# board.net
KiCad netlist of a schematic drawn in EAGLE
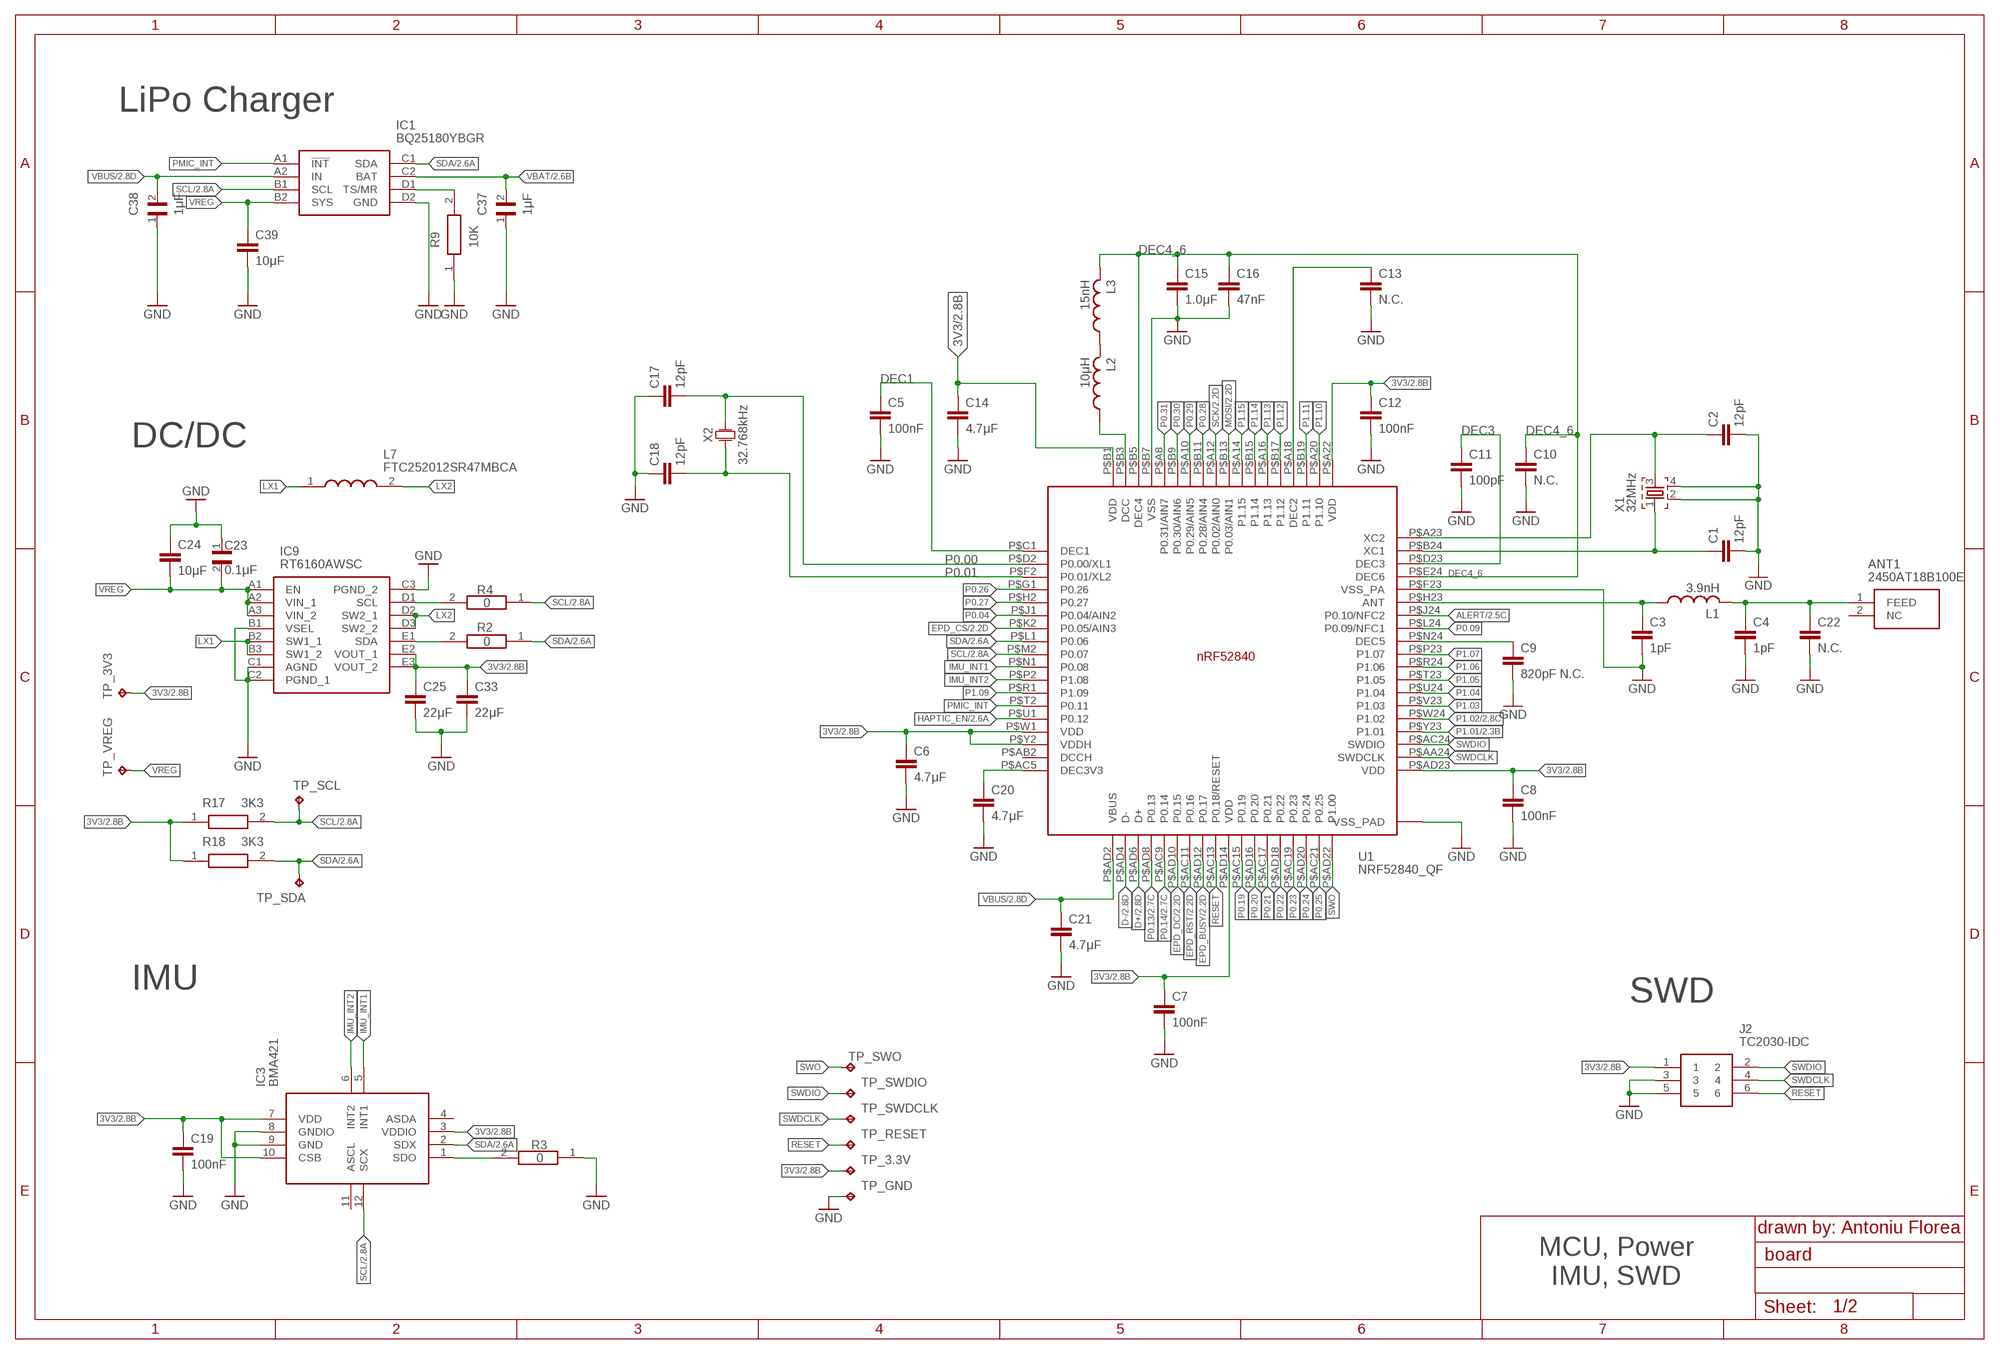
[diagram p0: schematic, sheet 1]
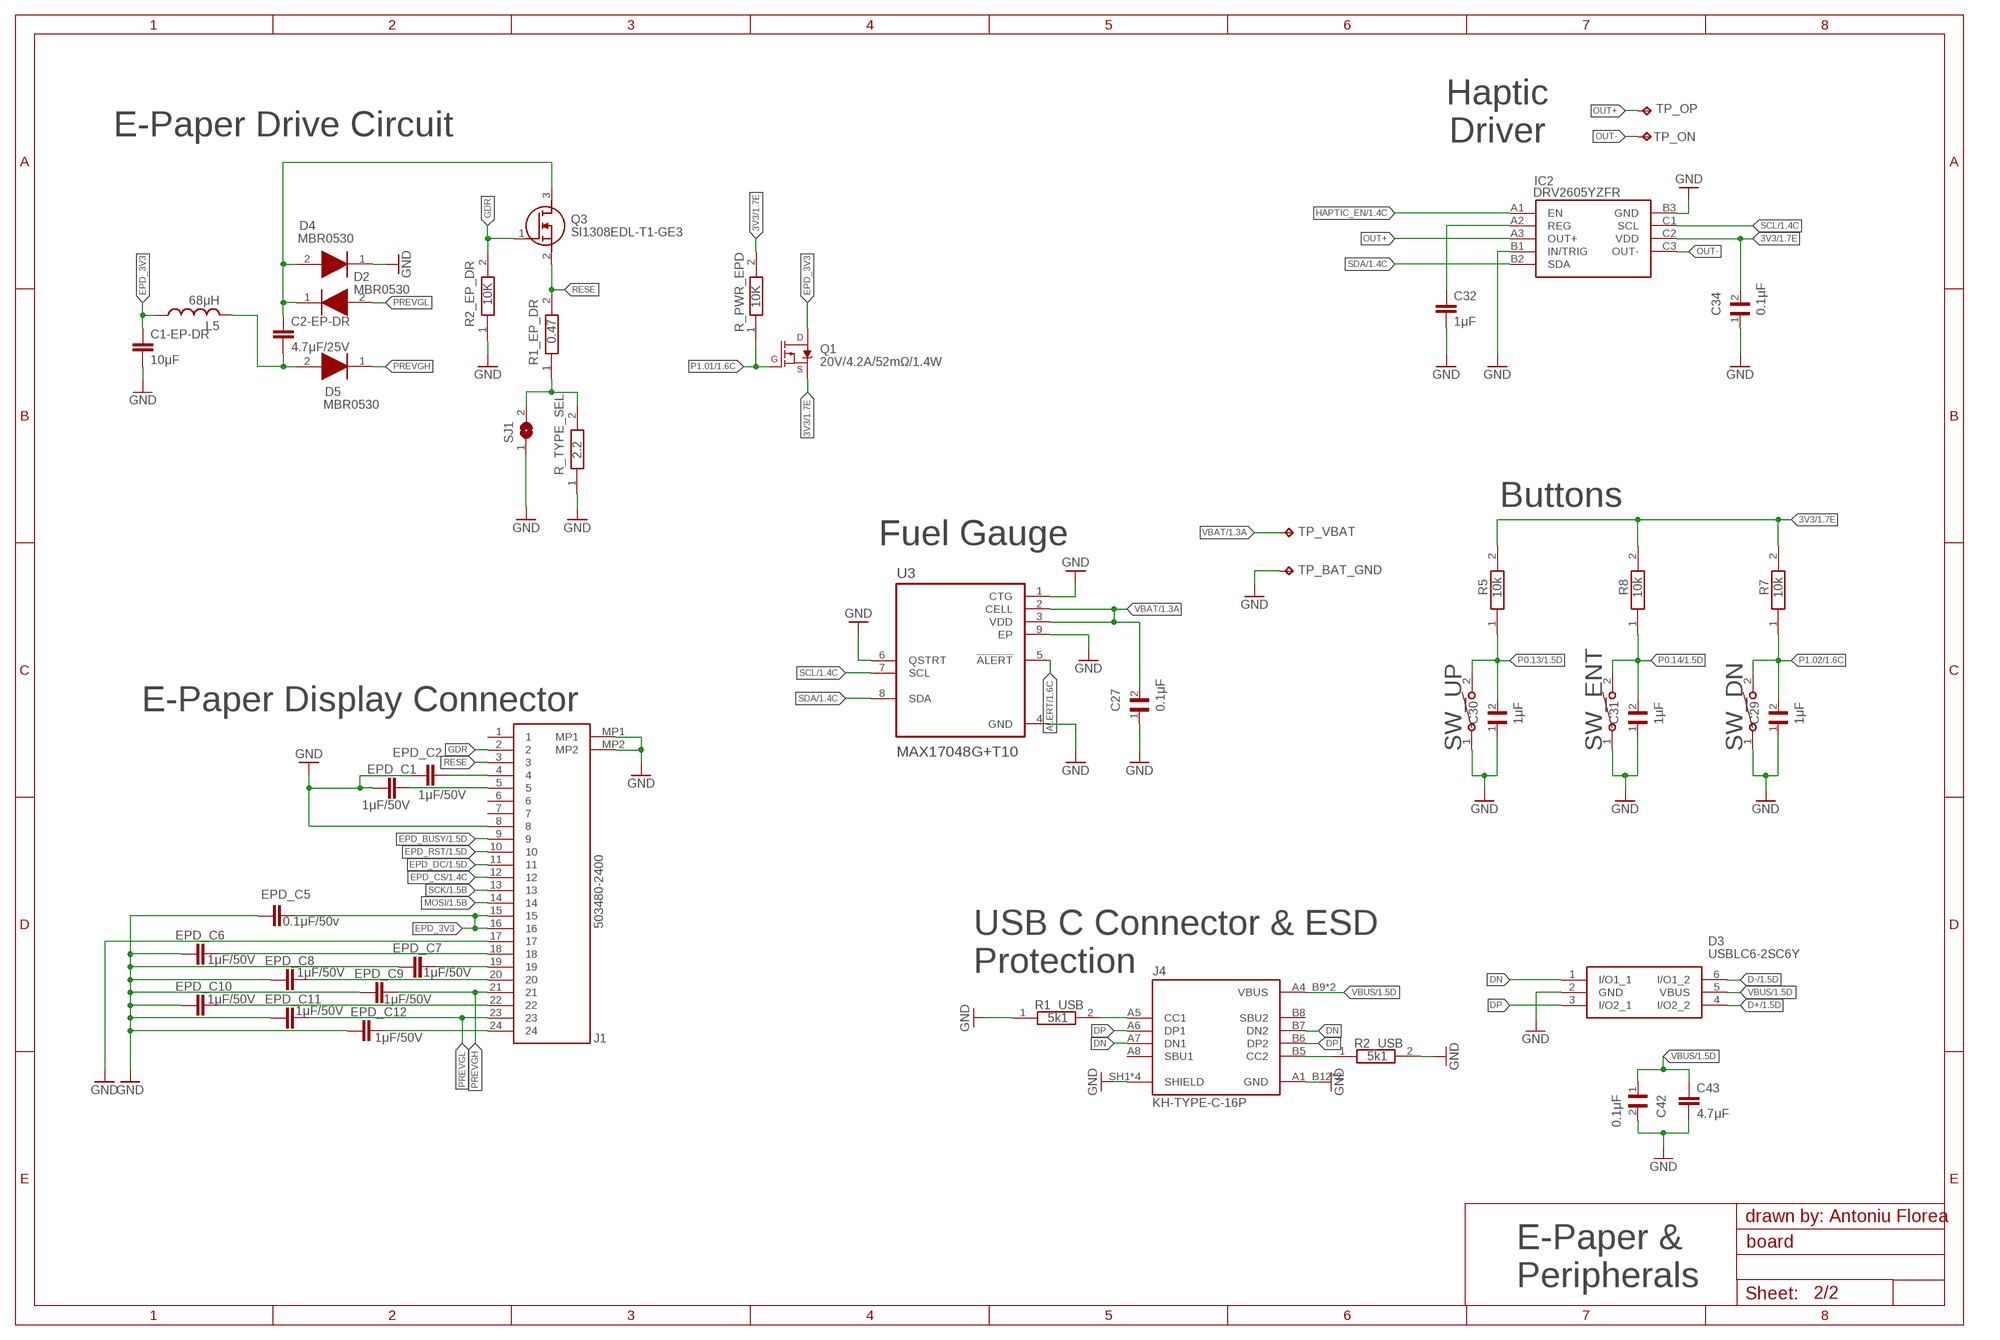
[diagram p1: schematic, sheet 2]

(export (version "E")
  (design (tool "Eeschema 10.0.6"))
  (components
    (comp (ref "C1-EP-DR")
      (value "10μF")
      (footprint "eagle-import:NORDIC_NRF_3_RESC0402_L")
      (libsource (lib "eagle-import") (part "NORDIC_NRF_3_CAPACITOR_0402_L"))
    )
    (comp (ref "C2-EP-DR")
      (value "4.7μF/25V")
      (footprint "eagle-import:NORDIC_NRF_3_RESC0402_L")
      (libsource (lib "eagle-import") (part "NORDIC_NRF_3_CAPACITOR_0402_L"))
    )
    (comp (ref "C27")
      (value "0.1μF")
      (footprint "eagle-import:GRM011R60J152KE01L_2_CAPC0201X13N")
      (fields (field (name "MF") "Murata") (field (name "MP") "GRM011R60J152KE01L"))
      (libsource (lib "eagle-import") (part "GRM011R60J152KE01L_2_GRM011R60J152KE01L"))
    )
    (comp (ref "C29")
      (value "1μF")
      (footprint "eagle-import:GRM011R60J152KE01L_2_CAPC0201X13N")
      (fields (field (name "MF") "Murata") (field (name "MP") "GRM011R60J152KE01L"))
      (libsource (lib "eagle-import") (part "GRM011R60J152KE01L_2_GRM011R60J152KE01L"))
    )
    (comp (ref "C30")
      (value "1μF")
      (footprint "eagle-import:GRM011R60J152KE01L_2_CAPC0201X13N")
      (fields (field (name "MF") "Murata") (field (name "MP") "GRM011R60J152KE01L"))
      (libsource (lib "eagle-import") (part "GRM011R60J152KE01L_2_GRM011R60J152KE01L"))
    )
    (comp (ref "C31")
      (value "1μF")
      (footprint "eagle-import:GRM011R60J152KE01L_2_CAPC0201X13N")
      (fields (field (name "MF") "Murata") (field (name "MP") "GRM011R60J152KE01L"))
      (libsource (lib "eagle-import") (part "GRM011R60J152KE01L_2_GRM011R60J152KE01L"))
    )
    (comp (ref "C32")
      (value "1μF")
      (footprint "eagle-import:NORDIC_NRF_3_RESC0402_L")
      (libsource (lib "eagle-import") (part "NORDIC_NRF_3_CAPACITOR_0402_L"))
    )
    (comp (ref "C34")
      (value "0.1μF")
      (footprint "eagle-import:GRM011R60J152KE01L_2_CAPC0201X13N")
      (fields (field (name "MF") "Murata") (field (name "MP") "GRM011R60J152KE01L"))
      (libsource (lib "eagle-import") (part "GRM011R60J152KE01L_2_GRM011R60J152KE01L"))
    )
    (comp (ref "C42")
      (value "0.1μF")
      (footprint "eagle-import:GRM011R60J152KE01L_2_CAPC0201X13N")
      (fields (field (name "MF") "Murata") (field (name "MP") "GRM011R60J152KE01L"))
      (libsource (lib "eagle-import") (part "GRM011R60J152KE01L_2_GRM011R60J152KE01L"))
    )
    (comp (ref "C43")
      (value "4.7μF")
      (footprint "eagle-import:NORDIC_NRF_3_RESC0402_L")
      (libsource (lib "eagle-import") (part "NORDIC_NRF_3_CAPACITOR_0402_L"))
    )
    (comp (ref "D2")
      (value "MBR0530")
      (footprint "eagle-import:ESP32_C6_LIBRARY_5_SOD3716X135N")
      (fields (field (name "MF") "ON Semiconductor"))
      (libsource (lib "eagle-import") (part "ESP32_C6_LIBRARY_5_MBR0530"))
    )
    (comp (ref "D3")
      (value "USBLC6-2SC6Y")
      (footprint "eagle-import:ESP32_C6_LIBRARY_3_SOT95P280X145-6N")
      (fields (field (name "MF") "STMicroelectronics"))
      (libsource (lib "eagle-import") (part "ESP32_C6_LIBRARY_3_USBLC6-2SC6Y"))
    )
    (comp (ref "D4")
      (value "MBR0530")
      (footprint "eagle-import:ESP32_C6_LIBRARY_5_SOD3716X135N")
      (fields (field (name "MF") "ON Semiconductor"))
      (libsource (lib "eagle-import") (part "ESP32_C6_LIBRARY_5_MBR0530"))
    )
    (comp (ref "D5")
      (value "MBR0530")
      (footprint "eagle-import:ESP32_C6_LIBRARY_5_SOD3716X135N")
      (fields (field (name "MF") "ON Semiconductor"))
      (libsource (lib "eagle-import") (part "ESP32_C6_LIBRARY_5_MBR0530"))
    )
    (comp (ref "EPD_C1")
      (value "1μF/50V")
      (footprint "eagle-import:NORDIC_NRF_3_RESC0402_L")
      (libsource (lib "eagle-import") (part "NORDIC_NRF_3_CAPACITOR_0402_L"))
    )
    (comp (ref "EPD_C2")
      (value "1μF/50V")
      (footprint "eagle-import:NORDIC_NRF_3_RESC0402_L")
      (libsource (lib "eagle-import") (part "NORDIC_NRF_3_CAPACITOR_0402_L"))
    )
    (comp (ref "EPD_C5")
      (value "0.1μF/50v")
      (footprint "eagle-import:NORDIC_NRF_3_RESC0201_L")
      (libsource (lib "eagle-import") (part "NORDIC_NRF_3_CAPACITOR_0201_L"))
    )
    (comp (ref "EPD_C6")
      (value "1μF/50V")
      (footprint "eagle-import:NORDIC_NRF_3_RESC0402_L")
      (libsource (lib "eagle-import") (part "NORDIC_NRF_3_CAPACITOR_0402_L"))
    )
    (comp (ref "EPD_C7")
      (value "1μF/50V")
      (footprint "eagle-import:NORDIC_NRF_3_RESC0402_L")
      (libsource (lib "eagle-import") (part "NORDIC_NRF_3_CAPACITOR_0402_L"))
    )
    (comp (ref "EPD_C8")
      (value "1μF/50V")
      (footprint "eagle-import:NORDIC_NRF_3_RESC0402_L")
      (libsource (lib "eagle-import") (part "NORDIC_NRF_3_CAPACITOR_0402_L"))
    )
    (comp (ref "EPD_C9")
      (value "1μF/50V")
      (footprint "eagle-import:NORDIC_NRF_3_RESC0402_L")
      (libsource (lib "eagle-import") (part "NORDIC_NRF_3_CAPACITOR_0402_L"))
    )
    (comp (ref "EPD_C10")
      (value "1μF/50V")
      (footprint "eagle-import:NORDIC_NRF_3_RESC0402_L")
      (libsource (lib "eagle-import") (part "NORDIC_NRF_3_CAPACITOR_0402_L"))
    )
    (comp (ref "EPD_C11")
      (value "1μF/50V")
      (footprint "eagle-import:NORDIC_NRF_3_RESC0402_L")
      (libsource (lib "eagle-import") (part "NORDIC_NRF_3_CAPACITOR_0402_L"))
    )
    (comp (ref "EPD_C12")
      (value "1μF/50V")
      (footprint "eagle-import:NORDIC_NRF_3_RESC0402_L")
      (libsource (lib "eagle-import") (part "NORDIC_NRF_3_CAPACITOR_0402_L"))
    )
    (comp (ref "IC2")
      (value "DRV2605YZFR")
      (footprint "eagle-import:DRV2605YZFR_BGA9C50P3X3_144X144X62")
      (libsource (lib "eagle-import") (part "DRV2605YZFR_DRV2605YZFR"))
    )
    (comp (ref "J1")
      (value "503480-2400")
      (footprint "eagle-import:503480-2400_5034802400")
      (fields (field (name "MOUSER_PART_NUMBER") "538-503480-2400"))
      (libsource (lib "eagle-import") (part "503480-2400_503480-2400"))
    )
    (comp (ref "J4")
      (value "KH-TYPE-C-16P")
      (footprint "eagle-import:KH-TYPE-C-16P_KINGHELM_KH-TYPE-C-16P")
      (fields (field (name "MF") "kinghelm"))
      (libsource (lib "eagle-import") (part "KH-TYPE-C-16P_KH-TYPE-C-16P"))
    )
    (comp (ref "L5")
      (value "68μH")
      (footprint "eagle-import:NORDIC_NRF_2_RESC0402_L")
      (libsource (lib "eagle-import") (part "NORDIC_NRF_2_INDUCTOR_0402_L"))
    )
    (comp (ref "Q1")
      (value "20V/4.2A/52mΩ/1.4W")
      (footprint "eagle-import:ESP32_C6_LIBRARY_4_ESP32_C6_LIBRARY_4_ESP32_C6_LIBRARY_4_ESP32_C6_LIBRARY_4_ESP32_WROVER_SPARKFUN-DISCRETESEMI_SOT23-3")
      (libsource (lib "eagle-import") (part "ESP32_C6_LIBRARY_4_ESP32_WROVER_SPARKFUN-DISCRETESEMI_MOSFET_PCH-DMG2305UX-7"))
    )
    (comp (ref "Q3")
      (value "SI1308EDL-T1-GE3")
      (footprint "eagle-import:ESP32_C6_LIBRARY_6_SOT65P210X110-3N")
      (fields (field (name "MF") "Vishay Siliconix"))
      (libsource (lib "eagle-import") (part "ESP32_C6_LIBRARY_6_SI1308EDL-T1-GE3"))
    )
    (comp (ref "R1_EP_DR")
      (value "0.47")
      (footprint "eagle-import:CPF0201D7K68C1_0201")
      (libsource (lib "eagle-import") (part "CPF0201D7K68C1_CPF0201D7K68C1"))
    )
    (comp (ref "R1_USB")
      (value "5k1")
      (footprint "eagle-import:ERA-1AEB3401C_0201")
      (libsource (lib "eagle-import") (part "ERA-1AEB3401C_CPF0201D7K68C1"))
    )
    (comp (ref "R2_EP_DR")
      (value "10K")
      (footprint "eagle-import:CPF0201D7K68C1_0201")
      (libsource (lib "eagle-import") (part "CPF0201D7K68C1_CPF0201D7K68C1"))
    )
    (comp (ref "R2_USB")
      (value "5k1")
      (footprint "eagle-import:ERA-1AEB3401C_0201")
      (libsource (lib "eagle-import") (part "ERA-1AEB3401C_CPF0201D7K68C1"))
    )
    (comp (ref "R5")
      (value "10k")
      (footprint "eagle-import:CPF0201D7K68C1_0201")
      (libsource (lib "eagle-import") (part "CPF0201D7K68C1_CPF0201D7K68C1"))
    )
    (comp (ref "R7")
      (value "10k")
      (footprint "eagle-import:CPF0201D7K68C1_0201")
      (libsource (lib "eagle-import") (part "CPF0201D7K68C1_CPF0201D7K68C1"))
    )
    (comp (ref "R8")
      (value "10k")
      (footprint "eagle-import:CPF0201D7K68C1_0201")
      (libsource (lib "eagle-import") (part "CPF0201D7K68C1_CPF0201D7K68C1"))
    )
    (comp (ref "R_PWR_EPD")
      (value "10K")
      (footprint "eagle-import:CPF0201D7K68C1_0201")
      (libsource (lib "eagle-import") (part "CPF0201D7K68C1_CPF0201D7K68C1"))
    )
    (comp (ref "R_TYPE_SEL")
      (value "2.2")
      (footprint "eagle-import:CPF0201D7K68C1_0201")
      (libsource (lib "eagle-import") (part "CPF0201D7K68C1_CPF0201D7K68C1"))
    )
    (comp (ref "SJ1")
      (value "ESP32_C6_LIBRARY_7_JUMPER_SJ")
      (footprint "eagle-import:ESP32_C6_LIBRARY_7_JUMPER_SJ")
      (libsource (lib "eagle-import") (part "ESP32_C6_LIBRARY_7_JUMPER_SJ"))
    )
    (comp (ref "SW_DN")
      (value "2025-10-22_07-23-44_LIBRARY_EVP-AKE31ASW_EVP-AKE31A_PAN")
      (footprint "eagle-import:2025-10-22_07-23-44_LIBRARY_SW_EVP-AKE31A_PAN")
      (fields
        (field (name "MANUFACTURER_PART_NUMBER") "EVP-AKE31A")
        (field (name "COPYRIGHT") "Copyright (C) 2025 Ultra Librarian. All rights reserved.")
      )
      (libsource (lib "eagle-import") (part "2025-10-22_07-23-44_LIBRARY_EVP-AKE31ASW_EVP-AKE31A_PAN"))
    )
    (comp (ref "SW_ENT")
      (value "2025-10-22_07-23-44_LIBRARY_EVP-AKE31ASW_EVP-AKE31A_PAN")
      (footprint "eagle-import:2025-10-22_07-23-44_LIBRARY_SW_EVP-AKE31A_PAN")
      (fields
        (field (name "MANUFACTURER_PART_NUMBER") "EVP-AKE31A")
        (field (name "COPYRIGHT") "Copyright (C) 2025 Ultra Librarian. All rights reserved.")
      )
      (libsource (lib "eagle-import") (part "2025-10-22_07-23-44_LIBRARY_EVP-AKE31ASW_EVP-AKE31A_PAN"))
    )
    (comp (ref "SW_UP")
      (value "2025-10-22_07-23-44_LIBRARY_EVP-AKE31ASW_EVP-AKE31A_PAN")
      (footprint "eagle-import:2025-10-22_07-23-44_LIBRARY_SW_EVP-AKE31A_PAN")
      (fields
        (field (name "MANUFACTURER_PART_NUMBER") "EVP-AKE31A")
        (field (name "COPYRIGHT") "Copyright (C) 2025 Ultra Librarian. All rights reserved.")
      )
      (libsource (lib "eagle-import") (part "2025-10-22_07-23-44_LIBRARY_EVP-AKE31ASW_EVP-AKE31A_PAN"))
    )
    (comp (ref "TP_BAT_GND")
      (value "HECTOR_WATCH_1_TPTP20R")
      (footprint "eagle-import:HECTOR_WATCH_1_TP20R")
      (libsource (lib "eagle-import") (part "HECTOR_WATCH_1_TPTP20R"))
    )
    (comp (ref "TP_ON")
      (value "HECTOR_WATCH_1_TPTP20R")
      (footprint "eagle-import:HECTOR_WATCH_1_TP20R")
      (libsource (lib "eagle-import") (part "HECTOR_WATCH_1_TPTP20R"))
    )
    (comp (ref "TP_OP")
      (value "HECTOR_WATCH_1_TPTP20R")
      (footprint "eagle-import:HECTOR_WATCH_1_TP20R")
      (libsource (lib "eagle-import") (part "HECTOR_WATCH_1_TPTP20R"))
    )
    (comp (ref "TP_VBAT")
      (value "HECTOR_WATCH_1_TPTP20R")
      (footprint "eagle-import:HECTOR_WATCH_1_TP20R")
      (libsource (lib "eagle-import") (part "HECTOR_WATCH_1_TPTP20R"))
    )
    (comp (ref "U3")
      (value "MAX17048G+T10")
      (footprint "eagle-import:ESP32_C6_LIBRARY_SON50P200X200X80-9N")
      (fields (field (name "MF") "Analog Devices"))
      (libsource (lib "eagle-import") (part "ESP32_C6_LIBRARY_MAX17048G+T10"))
    )
    (comp (ref "ANT1")
      (value "2450AT18B100E")
      (footprint "eagle-import:2450AT18B100E_ANTC3216X140N")
      (fields (field (name "MOUSER_PART_NUMBER") "609-2450AT18B100E"))
      (libsource (lib "eagle-import") (part "2450AT18B100E_2450AT18B100E"))
    )
    (comp (ref "C1")
      (value "12pF")
      (footprint "eagle-import:NORDIC_NRF_3_RESC0201_L")
      (libsource (lib "eagle-import") (part "NORDIC_NRF_3_CAPACITOR_0201_L"))
    )
    (comp (ref "C2")
      (value "12pF")
      (footprint "eagle-import:NORDIC_NRF_3_RESC0201_L")
      (libsource (lib "eagle-import") (part "NORDIC_NRF_3_CAPACITOR_0201_L"))
    )
    (comp (ref "C3")
      (value "1pF")
      (footprint "eagle-import:NORDIC_NRF_3_RESC0201_L")
      (libsource (lib "eagle-import") (part "NORDIC_NRF_3_CAPACITOR_0201_L"))
    )
    (comp (ref "C4")
      (value "1pF")
      (footprint "eagle-import:NORDIC_NRF_3_RESC0201_L")
      (libsource (lib "eagle-import") (part "NORDIC_NRF_3_CAPACITOR_0201_L"))
    )
    (comp (ref "C5")
      (value "100nF")
      (footprint "eagle-import:NORDIC_NRF_3_RESC0201_L")
      (libsource (lib "eagle-import") (part "NORDIC_NRF_3_CAPACITOR_0201_L"))
    )
    (comp (ref "C6")
      (value "4.7μF")
      (footprint "eagle-import:NORDIC_NRF_3_RESC0402_L")
      (libsource (lib "eagle-import") (part "NORDIC_NRF_3_CAPACITOR_0402_L"))
    )
    (comp (ref "C7")
      (value "100nF")
      (footprint "eagle-import:NORDIC_NRF_3_RESC0201_L")
      (libsource (lib "eagle-import") (part "NORDIC_NRF_3_CAPACITOR_0201_L"))
    )
    (comp (ref "C8")
      (value "100nF")
      (footprint "eagle-import:NORDIC_NRF_3_RESC0201_L")
      (libsource (lib "eagle-import") (part "NORDIC_NRF_3_CAPACITOR_0201_L"))
    )
    (comp (ref "C9")
      (value "820pF N.C.")
      (footprint "eagle-import:NORDIC_NRF_3_RESC0201_L")
      (libsource (lib "eagle-import") (part "NORDIC_NRF_3_CAPACITOR_0201_L"))
    )
    (comp (ref "C10")
      (value "N.C.")
      (footprint "eagle-import:NORDIC_NRF_3_RESC0201_L")
      (libsource (lib "eagle-import") (part "NORDIC_NRF_3_CAPACITOR_0201_L"))
    )
    (comp (ref "C11")
      (value "100pF")
      (footprint "eagle-import:NORDIC_NRF_3_RESC0201_L")
      (libsource (lib "eagle-import") (part "NORDIC_NRF_3_CAPACITOR_0201_L"))
    )
    (comp (ref "C12")
      (value "100nF")
      (footprint "eagle-import:NORDIC_NRF_3_RESC0201_L")
      (libsource (lib "eagle-import") (part "NORDIC_NRF_3_CAPACITOR_0201_L"))
    )
    (comp (ref "C13")
      (value "N.C.")
      (footprint "eagle-import:NORDIC_NRF_3_RESC0201_L")
      (libsource (lib "eagle-import") (part "NORDIC_NRF_3_CAPACITOR_0201_L"))
    )
    (comp (ref "C14")
      (value "4.7μF")
      (footprint "eagle-import:NORDIC_NRF_3_RESC0402_L")
      (libsource (lib "eagle-import") (part "NORDIC_NRF_3_CAPACITOR_0402_L"))
    )
    (comp (ref "C15")
      (value "1.0μF")
      (footprint "eagle-import:NORDIC_NRF_3_RESC0402_L")
      (libsource (lib "eagle-import") (part "NORDIC_NRF_3_CAPACITOR_0402_L"))
    )
    (comp (ref "C16")
      (value "47nF")
      (footprint "eagle-import:NORDIC_NRF_3_RESC0201_L")
      (libsource (lib "eagle-import") (part "NORDIC_NRF_3_CAPACITOR_0201_L"))
    )
    (comp (ref "C17")
      (value "12pF")
      (footprint "eagle-import:NORDIC_NRF_3_RESC0201_L")
      (libsource (lib "eagle-import") (part "NORDIC_NRF_3_CAPACITOR_0201_L"))
    )
    (comp (ref "C18")
      (value "12pF")
      (footprint "eagle-import:NORDIC_NRF_3_RESC0201_L")
      (libsource (lib "eagle-import") (part "NORDIC_NRF_3_CAPACITOR_0201_L"))
    )
    (comp (ref "C19")
      (value "100nF")
      (footprint "eagle-import:NORDIC_NRF_3_RESC0201_L")
      (libsource (lib "eagle-import") (part "NORDIC_NRF_3_CAPACITOR_0201_L"))
    )
    (comp (ref "C20")
      (value "4.7μF")
      (footprint "eagle-import:NORDIC_NRF_3_RESC0402_L")
      (libsource (lib "eagle-import") (part "NORDIC_NRF_3_CAPACITOR_0402_L"))
    )
    (comp (ref "C21")
      (value "4.7μF")
      (footprint "eagle-import:NORDIC_NRF_3_RESC0402_L")
      (libsource (lib "eagle-import") (part "NORDIC_NRF_3_CAPACITOR_0402_L"))
    )
    (comp (ref "C22")
      (value "N.C.")
      (footprint "eagle-import:NORDIC_NRF_3_RESC0201_L")
      (libsource (lib "eagle-import") (part "NORDIC_NRF_3_CAPACITOR_0201_L"))
    )
    (comp (ref "C23")
      (value "0.1μF")
      (footprint "eagle-import:GRM011R60J152KE01L_2_CAPC0201X13N")
      (fields (field (name "MF") "Murata") (field (name "MP") "GRM011R60J152KE01L"))
      (libsource (lib "eagle-import") (part "GRM011R60J152KE01L_2_GRM011R60J152KE01L"))
    )
    (comp (ref "C24")
      (value "10μF")
      (footprint "eagle-import:NORDIC_NRF_3_RESC0402_L")
      (libsource (lib "eagle-import") (part "NORDIC_NRF_3_CAPACITOR_0402_L"))
    )
    (comp (ref "C25")
      (value "22μF")
      (footprint "eagle-import:NORDIC_NRF_3_RESC0402_L")
      (libsource (lib "eagle-import") (part "NORDIC_NRF_3_CAPACITOR_0402_L"))
    )
    (comp (ref "C33")
      (value "22μF")
      (footprint "eagle-import:NORDIC_NRF_3_RESC0402_L")
      (libsource (lib "eagle-import") (part "NORDIC_NRF_3_CAPACITOR_0402_L"))
    )
    (comp (ref "C37")
      (value "1μF")
      (footprint "eagle-import:GRM011R60J152KE01L_2_CAPC0201X13N")
      (fields (field (name "MF") "Murata") (field (name "MP") "GRM011R60J152KE01L"))
      (libsource (lib "eagle-import") (part "GRM011R60J152KE01L_2_GRM011R60J152KE01L"))
    )
    (comp (ref "C38")
      (value "1μF")
      (footprint "eagle-import:GRM011R60J152KE01L_2_CAPC0201X13N")
      (fields (field (name "MF") "Murata") (field (name "MP") "GRM011R60J152KE01L"))
      (libsource (lib "eagle-import") (part "GRM011R60J152KE01L_2_GRM011R60J152KE01L"))
    )
    (comp (ref "C39")
      (value "10μF")
      (footprint "eagle-import:NORDIC_NRF_3_RESC0402_L")
      (libsource (lib "eagle-import") (part "NORDIC_NRF_3_CAPACITOR_0402_L"))
    )
    (comp (ref "IC1")
      (value "BQ25180YBGR")
      (footprint "eagle-import:BQ25180YBGR_BGA8C40P2X4_100X155X50")
      (fields (field (name "MOUSER_PART_NUMBER") "595-BQ25180YBGR"))
      (libsource (lib "eagle-import") (part "BQ25180YBGR_BQ25180YBGR"))
    )
    (comp (ref "IC3")
      (value "BMA421")
      (footprint "eagle-import:BMA423_BMA423")
      (fields (field (name "ARROW_PART_NUMBER") "BMA423") (field (name "MOUSER_PART_NUMBER") "262-BMA423"))
      (libsource (lib "eagle-import") (part "BMA423_BMA423"))
    )
    (comp (ref "IC9")
      (value "RT6160AWSC")
      (footprint "eagle-import:RT6160AWSC_BGA15C40P3X5_140X230X60")
      (fields (field (name "MOUSER_PART_NUMBER") "835-RT6160AWSC"))
      (libsource (lib "eagle-import") (part "RT6160AWSC_RT6160AWSC"))
    )
    (comp (ref "J2")
      (value "TC2030-IDC")
      (footprint "eagle-import:TC2030-IDC_TC2030IDC")
      (libsource (lib "eagle-import") (part "TC2030-IDC_TC2030-IDC"))
    )
    (comp (ref "L1")
      (value "3.9nH")
      (footprint "eagle-import:NORDIC_NRF_2_RESC0201_L")
      (libsource (lib "eagle-import") (part "NORDIC_NRF_2_INDUCTOR_0201_L"))
    )
    (comp (ref "L2")
      (value "10μH")
      (footprint "eagle-import:NORDIC_NRF_2_RESC0201_L")
      (libsource (lib "eagle-import") (part "NORDIC_NRF_2_INDUCTOR_0201_L"))
    )
    (comp (ref "L3")
      (value "15nH")
      (footprint "eagle-import:NORDIC_NRF_2_RESC0201_L")
      (libsource (lib "eagle-import") (part "NORDIC_NRF_2_INDUCTOR_0201_L"))
    )
    (comp (ref "L7")
      (value "FTC252012SR47MBCA")
      (footprint "eagle-import:MLP2016SR47MT0S1_INDC2016X100N")
      (libsource (lib "eagle-import") (part "MLP2016SR47MT0S1_FTC252012SR47MBCA"))
    )
    (comp (ref "R2")
      (value "0")
      (footprint "eagle-import:CPF0201D7K68C1_0201")
      (libsource (lib "eagle-import") (part "CPF0201D7K68C1_CPF0201D7K68C1"))
    )
    (comp (ref "R3")
      (value "0")
      (footprint "eagle-import:CPF0201D7K68C1_0201")
      (libsource (lib "eagle-import") (part "CPF0201D7K68C1_CPF0201D7K68C1"))
    )
    (comp (ref "R4")
      (value "0")
      (footprint "eagle-import:CPF0201D7K68C1_0201")
      (libsource (lib "eagle-import") (part "CPF0201D7K68C1_CPF0201D7K68C1"))
    )
    (comp (ref "R9")
      (value "10K")
      (footprint "eagle-import:ERA-1AEB3401C_0201")
      (libsource (lib "eagle-import") (part "ERA-1AEB3401C_CPF0201D7K68C1"))
    )
    (comp (ref "R17")
      (value "3K3")
      (footprint "eagle-import:CPF0201D7K68C1_0201")
      (libsource (lib "eagle-import") (part "CPF0201D7K68C1_CPF0201D7K68C1"))
    )
    (comp (ref "R18")
      (value "3K3")
      (footprint "eagle-import:CPF0201D7K68C1_0201")
      (libsource (lib "eagle-import") (part "CPF0201D7K68C1_CPF0201D7K68C1"))
    )
    (comp (ref "TP_3.3V")
      (value "HECTOR_WATCH_1_TPTP20R")
      (footprint "eagle-import:HECTOR_WATCH_1_TP20R")
      (libsource (lib "eagle-import") (part "HECTOR_WATCH_1_TPTP20R"))
    )
    (comp (ref "TP_3V3")
      (value "HECTOR_WATCH_1_TPTP20R")
      (footprint "eagle-import:HECTOR_WATCH_1_TP20R")
      (libsource (lib "eagle-import") (part "HECTOR_WATCH_1_TPTP20R"))
    )
    (comp (ref "TP_GND")
      (value "HECTOR_WATCH_1_TPTP20R")
      (footprint "eagle-import:HECTOR_WATCH_1_TP20R")
      (libsource (lib "eagle-import") (part "HECTOR_WATCH_1_TPTP20R"))
    )
    (comp (ref "TP_RESET")
      (value "HECTOR_WATCH_1_TPTP20R")
      (footprint "eagle-import:HECTOR_WATCH_1_TP20R")
      (libsource (lib "eagle-import") (part "HECTOR_WATCH_1_TPTP20R"))
    )
    (comp (ref "TP_SCL")
      (value "HECTOR_WATCH_1_TPTP20R")
      (footprint "eagle-import:HECTOR_WATCH_1_TP20R")
      (libsource (lib "eagle-import") (part "HECTOR_WATCH_1_TPTP20R"))
    )
    (comp (ref "TP_SDA")
      (value "HECTOR_WATCH_1_TPTP20R")
      (footprint "eagle-import:HECTOR_WATCH_1_TP20R")
      (libsource (lib "eagle-import") (part "HECTOR_WATCH_1_TPTP20R"))
    )
    (comp (ref "TP_SWDCLK")
      (value "HECTOR_WATCH_1_TPTP20R")
      (footprint "eagle-import:HECTOR_WATCH_1_TP20R")
      (libsource (lib "eagle-import") (part "HECTOR_WATCH_1_TPTP20R"))
    )
    (comp (ref "TP_SWDIO")
      (value "HECTOR_WATCH_1_TPTP20R")
      (footprint "eagle-import:HECTOR_WATCH_1_TP20R")
      (libsource (lib "eagle-import") (part "HECTOR_WATCH_1_TPTP20R"))
    )
    (comp (ref "TP_SWO")
      (value "HECTOR_WATCH_1_TPTP20R")
      (footprint "eagle-import:HECTOR_WATCH_1_TP20R")
      (libsource (lib "eagle-import") (part "HECTOR_WATCH_1_TPTP20R"))
    )
    (comp (ref "TP_VREG")
      (value "HECTOR_WATCH_1_TPTP20R")
      (footprint "eagle-import:HECTOR_WATCH_1_TP20R")
      (libsource (lib "eagle-import") (part "HECTOR_WATCH_1_TPTP20R"))
    )
    (comp (ref "U1")
      (value "NRF52840_QF")
      (footprint "eagle-import:NORDIC_NRF_4_AQFN50P700X700X85_HS-74N")
      (libsource (lib "eagle-import") (part "NORDIC_NRF_4_NRF52840_QF"))
    )
    (comp (ref "X1")
      (value "32MHz")
      (footprint "eagle-import:NORDIC_NRF_BT-XTAL_2016_N")
      (libsource (lib "eagle-import") (part "NORDIC_NRF_XTAL_32MHZ"))
    )
    (comp (ref "X2")
      (value "32.768kHz")
      (footprint "eagle-import:XTAL330X1051X90N")
      (fields
        (field (name "MANUFACTURER") "EPSON")
        (field (name "MPN") "FC-135 32.7680KA-A5")
        (field (name "TOLERANCE") "±20 ppm")
      )
      (libsource (lib "eagle-import") (part "FC-135"))
    )
  )
  (nets
    (net (code "1") (name "3V3") (class "Default")
      (node (ref "C12") (pin "1") (pinfunction "1_1") (pintype "passive"))
      (node (ref "C14") (pin "1") (pinfunction "1_1") (pintype "passive"))
      (node (ref "C19") (pin "1") (pinfunction "1_1") (pintype "passive"))
      (node (ref "C25") (pin "1") (pinfunction "1_1") (pintype "passive"))
      (node (ref "C33") (pin "1") (pinfunction "1_1") (pintype "passive"))
      (node (ref "C34") (pin "2") (pinfunction "2_2") (pintype "passive"))
      (node (ref "C6") (pin "1") (pinfunction "1_1") (pintype "passive"))
      (node (ref "C7") (pin "1") (pinfunction "1_1") (pintype "passive"))
      (node (ref "C8") (pin "1") (pinfunction "1_1") (pintype "passive"))
      (node (ref "IC2") (pin "C2") (pinfunction "VDD_C2") (pintype "bidirectional"))
      (node (ref "IC3") (pin "10") (pinfunction "CSB_10") (pintype "bidirectional"))
      (node (ref "IC3") (pin "3") (pinfunction "VDDIO_3") (pintype "bidirectional"))
      (node (ref "IC3") (pin "7") (pinfunction "VDD_7") (pintype "bidirectional"))
      (node (ref "IC9") (pin "E2") (pinfunction "VOUT_1_E2") (pintype "bidirectional"))
      (node (ref "IC9") (pin "E3") (pinfunction "VOUT_2_E3") (pintype "bidirectional"))
      (node (ref "J2") (pin "1") (pinfunction "1_1") (pintype "bidirectional"))
      (node (ref "Q1") (pin "2") (pinfunction "S_2") (pintype "bidirectional"))
      (node (ref "R17") (pin "1") (pinfunction "1_1") (pintype "bidirectional"))
      (node (ref "R18") (pin "1") (pinfunction "1_1") (pintype "bidirectional"))
      (node (ref "R5") (pin "2") (pinfunction "2_2") (pintype "bidirectional"))
      (node (ref "R7") (pin "2") (pinfunction "2_2") (pintype "bidirectional"))
      (node (ref "R8") (pin "2") (pinfunction "2_2") (pintype "bidirectional"))
      (node (ref "R_PWR_EPD") (pin "2") (pinfunction "2_2") (pintype "bidirectional"))
      (node (ref "TP_3.3V") (pin "TP") (pinfunction "TP_TP") (pintype "input"))
      (node (ref "TP_3V3") (pin "TP") (pinfunction "TP_TP") (pintype "input"))
      (node (ref "U1") (pin "P$A22") (pinfunction "VDD_P$A22") (pintype "power_in"))
      (node (ref "U1") (pin "P$AD14") (pinfunction "VDD_P$AD14") (pintype "power_in"))
      (node (ref "U1") (pin "P$AD23") (pinfunction "VDD_P$AD23") (pintype "power_in"))
      (node (ref "U1") (pin "P$B1") (pinfunction "VDD_P$B1") (pintype "power_in"))
      (node (ref "U1") (pin "P$W1") (pinfunction "VDD_P$W1") (pintype "power_in"))
      (node (ref "U1") (pin "P$Y2") (pinfunction "VDDH_P$Y2") (pintype "power_in"))
    )
    (net (code "2") (name "ALERT") (class "Default")
      (node (ref "U1") (pin "P$J24") (pinfunction "P0.10/NFC2_P$J24") (pintype "bidirectional"))
      (node (ref "U3") (pin "5") (pinfunction "~{ALERT}_5") (pintype "output"))
    )
    (net (code "3") (name "D+") (class "Default")
      (node (ref "D3") (pin "4") (pinfunction "I/O2_2_4") (pintype "bidirectional"))
      (node (ref "U1") (pin "P$AD6") (pinfunction "D+_P$AD6") (pintype "bidirectional"))
    )
    (net (code "4") (name "D-") (class "Default")
      (node (ref "D3") (pin "6") (pinfunction "I/O1_2_6") (pintype "bidirectional"))
      (node (ref "U1") (pin "P$AD4") (pinfunction "D-_P$AD4") (pintype "bidirectional"))
    )
    (net (code "5") (name "DEC1") (class "Default")
      (node (ref "C5") (pin "1") (pinfunction "1_1") (pintype "passive"))
      (node (ref "U1") (pin "P$C1") (pinfunction "DEC1_P$C1") (pintype "power_in"))
    )
    (net (code "6") (name "DEC3") (class "Default")
      (node (ref "C11") (pin "1") (pinfunction "1_1") (pintype "passive"))
      (node (ref "U1") (pin "P$D23") (pinfunction "DEC3_P$D23") (pintype "bidirectional"))
    )
    (net (code "7") (name "DEC4_6") (class "Default")
      (node (ref "C10") (pin "1") (pinfunction "1_1") (pintype "passive"))
      (node (ref "C15") (pin "1") (pinfunction "1_1") (pintype "passive"))
      (node (ref "C16") (pin "1") (pinfunction "1_1") (pintype "passive"))
      (node (ref "L3") (pin "2") (pinfunction "2_2") (pintype "passive"))
      (node (ref "U1") (pin "P$B5") (pinfunction "DEC4_P$B5") (pintype "power_in"))
      (node (ref "U1") (pin "P$E24") (pinfunction "DEC6_P$E24") (pintype "bidirectional"))
    )
    (net (code "8") (name "DN") (class "Default")
      (node (ref "D3") (pin "1") (pinfunction "I/O1_1_1") (pintype "bidirectional"))
      (node (ref "J4") (pin "A7") (pinfunction "DN1_A7") (pintype "bidirectional"))
      (node (ref "J4") (pin "B7") (pinfunction "DN2_B7") (pintype "bidirectional"))
    )
    (net (code "9") (name "DP") (class "Default")
      (node (ref "D3") (pin "3") (pinfunction "I/O2_1_3") (pintype "bidirectional"))
      (node (ref "J4") (pin "A6") (pinfunction "DP1_A6") (pintype "bidirectional"))
      (node (ref "J4") (pin "B6") (pinfunction "DP2_B6") (pintype "bidirectional"))
    )
    (net (code "10") (name "EPD_3V3") (class "Default")
      (node (ref "C1-EP-DR") (pin "1") (pinfunction "1_1") (pintype "passive"))
      (node (ref "EPD_C5") (pin "2") (pinfunction "2_2") (pintype "passive"))
      (node (ref "J1") (pin "15") (pinfunction "15_15") (pintype "bidirectional"))
      (node (ref "J1") (pin "16") (pinfunction "16_16") (pintype "bidirectional"))
      (node (ref "L5") (pin "1") (pinfunction "1_1") (pintype "passive"))
      (node (ref "Q1") (pin "3") (pinfunction "D_3") (pintype "bidirectional"))
    )
    (net (code "11") (name "EPD_BUSY") (class "Default")
      (node (ref "J1") (pin "9") (pinfunction "9_9") (pintype "bidirectional"))
      (node (ref "U1") (pin "P$AD12") (pinfunction "P0.17_P$AD12") (pintype "bidirectional"))
    )
    (net (code "12") (name "EPD_CS") (class "Default")
      (node (ref "J1") (pin "12") (pinfunction "12_12") (pintype "bidirectional"))
      (node (ref "U1") (pin "P$K2") (pinfunction "P0.05/AIN3_P$K2") (pintype "bidirectional"))
    )
    (net (code "13") (name "EPD_DC") (class "Default")
      (node (ref "J1") (pin "11") (pinfunction "11_11") (pintype "bidirectional"))
      (node (ref "U1") (pin "P$AD10") (pinfunction "P0.15_P$AD10") (pintype "bidirectional"))
    )
    (net (code "14") (name "EPD_RST") (class "Default")
      (node (ref "J1") (pin "10") (pinfunction "10_10") (pintype "bidirectional"))
      (node (ref "U1") (pin "P$AC11") (pinfunction "P0.16_P$AC11") (pintype "bidirectional"))
    )
    (net (code "15") (name "GDR") (class "Default")
      (node (ref "J1") (pin "2") (pinfunction "2_2") (pintype "bidirectional"))
      (node (ref "Q3") (pin "1") (pinfunction "G_1") (pintype "bidirectional"))
      (node (ref "R2_EP_DR") (pin "2") (pinfunction "2_2") (pintype "bidirectional"))
    )
    (net (code "16") (name "GND") (class "Default")
      (node (ref "C1") (pin "2") (pinfunction "2_2") (pintype "passive"))
      (node (ref "C1-EP-DR") (pin "2") (pinfunction "2_2") (pintype "passive"))
      (node (ref "C10") (pin "2") (pinfunction "2_2") (pintype "passive"))
      (node (ref "C11") (pin "2") (pinfunction "2_2") (pintype "passive"))
      (node (ref "C12") (pin "2") (pinfunction "2_2") (pintype "passive"))
      (node (ref "C13") (pin "2") (pinfunction "2_2") (pintype "passive"))
      (node (ref "C14") (pin "2") (pinfunction "2_2") (pintype "passive"))
      (node (ref "C15") (pin "2") (pinfunction "2_2") (pintype "passive"))
      (node (ref "C16") (pin "2") (pinfunction "2_2") (pintype "passive"))
      (node (ref "C17") (pin "1") (pinfunction "1_1") (pintype "passive"))
      (node (ref "C18") (pin "1") (pinfunction "1_1") (pintype "passive"))
      (node (ref "C19") (pin "2") (pinfunction "2_2") (pintype "passive"))
      (node (ref "C2") (pin "2") (pinfunction "2_2") (pintype "passive"))
      (node (ref "C20") (pin "2") (pinfunction "2_2") (pintype "passive"))
      (node (ref "C21") (pin "2") (pinfunction "2_2") (pintype "passive"))
      (node (ref "C22") (pin "2") (pinfunction "2_2") (pintype "passive"))
      (node (ref "C23") (pin "1") (pinfunction "1_1") (pintype "passive"))
      (node (ref "C24") (pin "1") (pinfunction "1_1") (pintype "passive"))
      (node (ref "C25") (pin "2") (pinfunction "2_2") (pintype "passive"))
      (node (ref "C27") (pin "1") (pinfunction "1_1") (pintype "passive"))
      (node (ref "C29") (pin "1") (pinfunction "1_1") (pintype "passive"))
      (node (ref "C3") (pin "2") (pinfunction "2_2") (pintype "passive"))
      (node (ref "C30") (pin "1") (pinfunction "1_1") (pintype "passive"))
      (node (ref "C31") (pin "1") (pinfunction "1_1") (pintype "passive"))
      (node (ref "C32") (pin "2") (pinfunction "2_2") (pintype "passive"))
      (node (ref "C33") (pin "2") (pinfunction "2_2") (pintype "passive"))
      (node (ref "C34") (pin "1") (pinfunction "1_1") (pintype "passive"))
      (node (ref "C37") (pin "1") (pinfunction "1_1") (pintype "passive"))
      (node (ref "C38") (pin "1") (pinfunction "1_1") (pintype "passive"))
      (node (ref "C39") (pin "2") (pinfunction "2_2") (pintype "passive"))
      (node (ref "C4") (pin "2") (pinfunction "2_2") (pintype "passive"))
      (node (ref "C42") (pin "2") (pinfunction "2_2") (pintype "passive"))
      (node (ref "C43") (pin "2") (pinfunction "2_2") (pintype "passive"))
      (node (ref "C5") (pin "2") (pinfunction "2_2") (pintype "passive"))
      (node (ref "C6") (pin "2") (pinfunction "2_2") (pintype "passive"))
      (node (ref "C7") (pin "2") (pinfunction "2_2") (pintype "passive"))
      (node (ref "C8") (pin "2") (pinfunction "2_2") (pintype "passive"))
      (node (ref "C9") (pin "2") (pinfunction "2_2") (pintype "passive"))
      (node (ref "D3") (pin "2") (pinfunction "GND_2") (pintype "bidirectional"))
      (node (ref "D4") (pin "1") (pinfunction "K_1") (pintype "bidirectional"))
      (node (ref "EPD_C1") (pin "2") (pinfunction "2_2") (pintype "passive"))
      (node (ref "EPD_C10") (pin "2") (pinfunction "2_2") (pintype "passive"))
      (node (ref "EPD_C11") (pin "2") (pinfunction "2_2") (pintype "passive"))
      (node (ref "EPD_C12") (pin "2") (pinfunction "2_2") (pintype "passive"))
      (node (ref "EPD_C2") (pin "2") (pinfunction "2_2") (pintype "passive"))
      (node (ref "EPD_C5") (pin "1") (pinfunction "1_1") (pintype "passive"))
      (node (ref "EPD_C6") (pin "2") (pinfunction "2_2") (pintype "passive"))
      (node (ref "EPD_C7") (pin "2") (pinfunction "2_2") (pintype "passive"))
      (node (ref "EPD_C8") (pin "2") (pinfunction "2_2") (pintype "passive"))
      (node (ref "EPD_C9") (pin "2") (pinfunction "2_2") (pintype "passive"))
      (node (ref "IC1") (pin "D2") (pinfunction "GND_D2") (pintype "bidirectional"))
      (node (ref "IC2") (pin "B1") (pinfunction "IN/TRIG_B1") (pintype "bidirectional"))
      (node (ref "IC2") (pin "B3") (pinfunction "GND_B3") (pintype "bidirectional"))
      (node (ref "IC3") (pin "8") (pinfunction "GNDIO_8") (pintype "bidirectional"))
      (node (ref "IC3") (pin "9") (pinfunction "GND_9") (pintype "bidirectional"))
      (node (ref "IC9") (pin "B1") (pinfunction "VSEL_B1") (pintype "bidirectional"))
      (node (ref "IC9") (pin "C1") (pinfunction "AGND_C1") (pintype "bidirectional"))
      (node (ref "IC9") (pin "C2") (pinfunction "PGND_1_C2") (pintype "bidirectional"))
      (node (ref "IC9") (pin "C3") (pinfunction "PGND_2_C3") (pintype "bidirectional"))
      (node (ref "J1") (pin "17") (pinfunction "17_17") (pintype "bidirectional"))
      (node (ref "J1") (pin "8") (pinfunction "8_8") (pintype "bidirectional"))
      (node (ref "J1") (pin "MP1") (pinfunction "MP1_MP1") (pintype "bidirectional"))
      (node (ref "J1") (pin "MP2") (pinfunction "MP2_MP2") (pintype "bidirectional"))
      (node (ref "J2") (pin "3") (pinfunction "3_3") (pintype "bidirectional"))
      (node (ref "J2") (pin "5") (pinfunction "5_5") (pintype "bidirectional"))
      (node (ref "J4") (pin "A12_B1") (pinfunction "GND_A12_B1") (pintype "power_in"))
      (node (ref "J4") (pin "A1_B12") (pinfunction "GND_A1_B12") (pintype "power_in"))
      (node (ref "J4") (pin "SH1") (pinfunction "SHIELD_SH1") (pintype "passive"))
      (node (ref "J4") (pin "SH2") (pinfunction "SHIELD_SH2") (pintype "passive"))
      (node (ref "J4") (pin "SH3") (pinfunction "SHIELD_SH3") (pintype "passive"))
      (node (ref "J4") (pin "SH4") (pinfunction "SHIELD_SH4") (pintype "passive"))
      (node (ref "R1_USB") (pin "1") (pinfunction "1_1") (pintype "bidirectional"))
      (node (ref "R2_EP_DR") (pin "1") (pinfunction "1_1") (pintype "bidirectional"))
      (node (ref "R2_USB") (pin "2") (pinfunction "2_2") (pintype "bidirectional"))
      (node (ref "R3") (pin "1") (pinfunction "1_1") (pintype "bidirectional"))
      (node (ref "R9") (pin "1") (pinfunction "1_1") (pintype "bidirectional"))
      (node (ref "R_TYPE_SEL") (pin "1") (pinfunction "1_1") (pintype "bidirectional"))
      (node (ref "SJ1") (pin "1") (pinfunction "1_1") (pintype "passive"))
      (node (ref "SW_DN") (pin "1") (pinfunction "1_1") (pintype "passive"))
      (node (ref "SW_ENT") (pin "1") (pinfunction "1_1") (pintype "passive"))
      (node (ref "SW_UP") (pin "1") (pinfunction "1_1") (pintype "passive"))
      (node (ref "TP_BAT_GND") (pin "TP") (pinfunction "TP_TP") (pintype "input"))
      (node (ref "TP_GND") (pin "TP") (pinfunction "TP_TP") (pintype "input"))
      (node (ref "U1") (pin "P$74") (pinfunction "VSS_PAD_P$74") (pintype "bidirectional"))
      (node (ref "U1") (pin "P$75") (pinfunction "VSS_PAD_P$75") (pintype "bidirectional"))
      (node (ref "U1") (pin "P$76") (pinfunction "VSS_PAD_P$76") (pintype "bidirectional"))
      (node (ref "U1") (pin "P$77") (pinfunction "VSS_PAD_P$77") (pintype "bidirectional"))
      (node (ref "U1") (pin "P$78") (pinfunction "VSS_PAD_P$78") (pintype "bidirectional"))
      (node (ref "U1") (pin "P$79") (pinfunction "VSS_PAD_P$79") (pintype "bidirectional"))
      (node (ref "U1") (pin "P$80") (pinfunction "VSS_PAD_P$80") (pintype "bidirectional"))
      (node (ref "U1") (pin "P$81") (pinfunction "VSS_PAD_P$81") (pintype "bidirectional"))
      (node (ref "U1") (pin "P$82") (pinfunction "VSS_PAD_P$82") (pintype "bidirectional"))
      (node (ref "U1") (pin "P$83") (pinfunction "VSS_PAD_P$83") (pintype "bidirectional"))
      (node (ref "U1") (pin "P$84") (pinfunction "VSS_PAD_P$84") (pintype "bidirectional"))
      (node (ref "U1") (pin "P$85") (pinfunction "VSS_PAD_P$85") (pintype "bidirectional"))
      (node (ref "U1") (pin "P$86") (pinfunction "VSS_PAD_P$86") (pintype "bidirectional"))
      (node (ref "U1") (pin "P$87") (pinfunction "VSS_PAD_P$87") (pintype "bidirectional"))
      (node (ref "U1") (pin "P$88") (pinfunction "VSS_PAD_P$88") (pintype "bidirectional"))
      (node (ref "U1") (pin "P$89") (pinfunction "VSS_PAD_P$89") (pintype "bidirectional"))
      (node (ref "U1") (pin "P$90") (pinfunction "VSS_PAD_P$90") (pintype "bidirectional"))
      (node (ref "U1") (pin "P$B7") (pinfunction "VSS_P$B7") (pintype "power_in"))
      (node (ref "U1") (pin "P$F23") (pinfunction "VSS_PA_P$F23") (pintype "bidirectional"))
      (node (ref "U3") (pin "1") (pinfunction "CTG_1") (pintype "power_in"))
      (node (ref "U3") (pin "4") (pinfunction "GND_4") (pintype "power_in"))
      (node (ref "U3") (pin "6") (pinfunction "QSTRT_6") (pintype "input"))
      (node (ref "U3") (pin "9") (pinfunction "EP_9") (pintype "power_in"))
      (node (ref "X1") (pin "2") (pinfunction "2_2") (pintype "passive"))
      (node (ref "X1") (pin "4") (pinfunction "4_4") (pintype "passive"))
    )
    (net (code "17") (name "HAPTIC_EN") (class "Default")
      (node (ref "IC2") (pin "A1") (pinfunction "EN_A1") (pintype "bidirectional"))
      (node (ref "U1") (pin "P$U1") (pinfunction "P0.12_P$U1") (pintype "bidirectional"))
    )
    (net (code "18") (name "IMU_INT1") (class "Default")
      (node (ref "IC3") (pin "5") (pinfunction "INT1_5") (pintype "bidirectional"))
      (node (ref "U1") (pin "P$N1") (pinfunction "P0.08_P$N1") (pintype "bidirectional"))
    )
    (net (code "19") (name "IMU_INT2") (class "Default")
      (node (ref "IC3") (pin "6") (pinfunction "INT2_6") (pintype "bidirectional"))
      (node (ref "U1") (pin "P$P2") (pinfunction "P1.08_P$P2") (pintype "bidirectional"))
    )
    (net (code "20") (name "LX1") (class "Default")
      (node (ref "IC9") (pin "B2") (pinfunction "SW1_1_B2") (pintype "bidirectional"))
      (node (ref "IC9") (pin "B3") (pinfunction "SW1_2_B3") (pintype "bidirectional"))
      (node (ref "L7") (pin "1") (pinfunction "1_1") (pintype "bidirectional"))
    )
    (net (code "21") (name "LX2") (class "Default")
      (node (ref "IC9") (pin "D2") (pinfunction "SW2_1_D2") (pintype "bidirectional"))
      (node (ref "IC9") (pin "D3") (pinfunction "SW2_2_D3") (pintype "bidirectional"))
      (node (ref "L7") (pin "2") (pinfunction "2_2") (pintype "bidirectional"))
    )
    (net (code "22") (name "MOSI") (class "Default")
      (node (ref "J1") (pin "14") (pinfunction "14_14") (pintype "bidirectional"))
      (node (ref "U1") (pin "P$B13") (pinfunction "P0.03/AIN1_P$B13") (pintype "bidirectional"))
    )
    (net (code "23") (name "Net-(ANT1-FEED)") (class "Default")
      (node (ref "ANT1") (pin "1") (pinfunction "FEED_1") (pintype "input"))
      (node (ref "C22") (pin "1") (pinfunction "1_1") (pintype "passive"))
      (node (ref "C4") (pin "1") (pinfunction "1_1") (pintype "passive"))
      (node (ref "L1") (pin "2") (pinfunction "2_2") (pintype "passive"))
    )
    (net (code "24") (name "Net-(D2-K)") (class "Default")
      (node (ref "C2-EP-DR") (pin "1") (pinfunction "1_1") (pintype "passive"))
      (node (ref "D2") (pin "1") (pinfunction "K_1") (pintype "bidirectional"))
      (node (ref "D4") (pin "2") (pinfunction "A_2") (pintype "bidirectional"))
      (node (ref "Q3") (pin "3") (pinfunction "D_3") (pintype "bidirectional"))
    )
    (net (code "25") (name "Net-(D5-A)") (class "Default")
      (node (ref "C2-EP-DR") (pin "2") (pinfunction "2_2") (pintype "passive"))
      (node (ref "D5") (pin "2") (pinfunction "A_2") (pintype "bidirectional"))
      (node (ref "L5") (pin "2") (pinfunction "2_2") (pintype "passive"))
    )
    (net (code "26") (name "Net-(EPD_C1-Pad1)") (class "Default")
      (node (ref "EPD_C1") (pin "1") (pinfunction "1_1") (pintype "passive"))
      (node (ref "J1") (pin "5") (pinfunction "5_5") (pintype "bidirectional"))
    )
    (net (code "27") (name "Net-(EPD_C2-Pad1)") (class "Default")
      (node (ref "EPD_C2") (pin "1") (pinfunction "1_1") (pintype "passive"))
      (node (ref "J1") (pin "4") (pinfunction "4_4") (pintype "bidirectional"))
    )
    (net (code "28") (name "Net-(EPD_C6-Pad1)") (class "Default")
      (node (ref "EPD_C6") (pin "1") (pinfunction "1_1") (pintype "passive"))
      (node (ref "J1") (pin "18") (pinfunction "18_18") (pintype "bidirectional"))
    )
    (net (code "29") (name "Net-(EPD_C7-Pad1)") (class "Default")
      (node (ref "EPD_C7") (pin "1") (pinfunction "1_1") (pintype "passive"))
      (node (ref "J1") (pin "19") (pinfunction "19_19") (pintype "bidirectional"))
    )
    (net (code "30") (name "Net-(EPD_C8-Pad1)") (class "Default")
      (node (ref "EPD_C8") (pin "1") (pinfunction "1_1") (pintype "passive"))
      (node (ref "J1") (pin "20") (pinfunction "20_20") (pintype "bidirectional"))
    )
    (net (code "31") (name "Net-(EPD_C10-Pad1)") (class "Default")
      (node (ref "EPD_C10") (pin "1") (pinfunction "1_1") (pintype "passive"))
      (node (ref "J1") (pin "22") (pinfunction "22_22") (pintype "bidirectional"))
    )
    (net (code "32") (name "Net-(EPD_C12-Pad1)") (class "Default")
      (node (ref "EPD_C12") (pin "1") (pinfunction "1_1") (pintype "passive"))
      (node (ref "J1") (pin "24") (pinfunction "24_24") (pintype "bidirectional"))
    )
    (net (code "33") (name "Net-(IC1-TS{slash}MR)") (class "Default")
      (node (ref "IC1") (pin "D1") (pinfunction "TS/MR_D1") (pintype "bidirectional"))
      (node (ref "R9") (pin "2") (pinfunction "2_2") (pintype "bidirectional"))
    )
    (net (code "34") (name "Net-(IC2-REG)") (class "Default")
      (node (ref "C32") (pin "1") (pinfunction "1_1") (pintype "passive"))
      (node (ref "IC2") (pin "A2") (pinfunction "REG_A2") (pintype "bidirectional"))
    )
    (net (code "35") (name "Net-(IC3-SDO)") (class "Default")
      (node (ref "IC3") (pin "1") (pinfunction "SDO_1") (pintype "bidirectional"))
      (node (ref "R3") (pin "2") (pinfunction "2_2") (pintype "bidirectional"))
    )
    (net (code "36") (name "Net-(IC9-SCL)") (class "Default")
      (node (ref "IC9") (pin "D1") (pinfunction "SCL_D1") (pintype "bidirectional"))
      (node (ref "R4") (pin "2") (pinfunction "2_2") (pintype "bidirectional"))
    )
    (net (code "37") (name "Net-(IC9-SDA)") (class "Default")
      (node (ref "IC9") (pin "E1") (pinfunction "SDA_E1") (pintype "bidirectional"))
      (node (ref "R2") (pin "2") (pinfunction "2_2") (pintype "bidirectional"))
    )
    (net (code "38") (name "Net-(J4-CC1)") (class "Default")
      (node (ref "J4") (pin "A5") (pinfunction "CC1_A5") (pintype "bidirectional"))
      (node (ref "R1_USB") (pin "2") (pinfunction "2_2") (pintype "bidirectional"))
    )
    (net (code "39") (name "Net-(J4-CC2)") (class "Default")
      (node (ref "J4") (pin "B5") (pinfunction "CC2_B5") (pintype "bidirectional"))
      (node (ref "R2_USB") (pin "1") (pinfunction "1_1") (pintype "bidirectional"))
    )
    (net (code "40") (name "Net-(L2-Pad2)") (class "Default")
      (node (ref "L2") (pin "2") (pinfunction "2_2") (pintype "passive"))
      (node (ref "L3") (pin "1") (pinfunction "1_1") (pintype "passive"))
    )
    (net (code "41") (name "Net-(R1_EP_DR-Pad1)") (class "Default")
      (node (ref "R1_EP_DR") (pin "1") (pinfunction "1_1") (pintype "bidirectional"))
      (node (ref "R_TYPE_SEL") (pin "2") (pinfunction "2_2") (pintype "bidirectional"))
      (node (ref "SJ1") (pin "2") (pinfunction "2_2") (pintype "passive"))
    )
    (net (code "42") (name "Net-(U1-ANT)") (class "Default")
      (node (ref "C3") (pin "1") (pinfunction "1_1") (pintype "passive"))
      (node (ref "L1") (pin "1") (pinfunction "1_1") (pintype "passive"))
      (node (ref "U1") (pin "P$H23") (pinfunction "ANT_P$H23") (pintype "bidirectional"))
    )
    (net (code "43") (name "Net-(U1-DCC)") (class "Default")
      (node (ref "L2") (pin "1") (pinfunction "1_1") (pintype "passive"))
      (node (ref "U1") (pin "P$B3") (pinfunction "DCC_P$B3") (pintype "output"))
    )
    (net (code "44") (name "Net-(U1-DEC2)") (class "Default")
      (node (ref "C13") (pin "1") (pinfunction "1_1") (pintype "passive"))
      (node (ref "U1") (pin "P$A18") (pinfunction "DEC2_P$A18") (pintype "bidirectional"))
    )
    (net (code "45") (name "Net-(U1-DEC3V3)") (class "Default")
      (node (ref "C20") (pin "1") (pinfunction "1_1") (pintype "passive"))
      (node (ref "U1") (pin "P$AC5") (pinfunction "DEC3V3_P$AC5") (pintype "bidirectional"))
    )
    (net (code "46") (name "Net-(U1-DEC5)") (class "Default")
      (node (ref "C9") (pin "1") (pinfunction "1_1") (pintype "passive"))
      (node (ref "U1") (pin "P$N24") (pinfunction "DEC5_P$N24") (pintype "bidirectional"))
    )
    (net (code "47") (name "Net-(U1-XC1)") (class "Default")
      (node (ref "C1") (pin "1") (pinfunction "1_1") (pintype "passive"))
      (node (ref "U1") (pin "P$B24") (pinfunction "XC1_P$B24") (pintype "input"))
      (node (ref "X1") (pin "1") (pinfunction "1_1") (pintype "passive"))
    )
    (net (code "48") (name "Net-(U1-XC2)") (class "Default")
      (node (ref "C2") (pin "1") (pinfunction "1_1") (pintype "passive"))
      (node (ref "U1") (pin "P$A23") (pinfunction "XC2_P$A23") (pintype "output"))
      (node (ref "X1") (pin "3") (pinfunction "3_3") (pintype "passive"))
    )
    (net (code "49") (name "OUT+") (class "Default")
      (node (ref "IC2") (pin "A3") (pinfunction "OUT+_A3") (pintype "bidirectional"))
      (node (ref "TP_OP") (pin "TP") (pinfunction "TP_TP") (pintype "input"))
    )
    (net (code "50") (name "OUT-") (class "Default")
      (node (ref "IC2") (pin "C3") (pinfunction "OUT-_C3") (pintype "bidirectional"))
      (node (ref "TP_ON") (pin "TP") (pinfunction "TP_TP") (pintype "input"))
    )
    (net (code "51") (name "P0.00") (class "Default")
      (node (ref "C17") (pin "2") (pinfunction "2_2") (pintype "passive"))
      (node (ref "U1") (pin "P$D2") (pinfunction "P0.00/XL1_P$D2") (pintype "bidirectional"))
      (node (ref "X2") (pin "2") (pinfunction "2_2") (pintype "passive"))
    )
    (net (code "52") (name "P0.01") (class "Default")
      (node (ref "C18") (pin "2") (pinfunction "2_2") (pintype "passive"))
      (node (ref "U1") (pin "P$F2") (pinfunction "P0.01/XL2_P$F2") (pintype "bidirectional"))
      (node (ref "X2") (pin "1") (pinfunction "1_1") (pintype "passive"))
    )
    (net (code "53") (name "P0.04") (class "Default")
      (node (ref "U1") (pin "P$J1") (pinfunction "P0.04/AIN2_P$J1") (pintype "bidirectional"))
    )
    (net (code "54") (name "P0.09") (class "Default")
      (node (ref "U1") (pin "P$L24") (pinfunction "P0.09/NFC1_P$L24") (pintype "bidirectional"))
    )
    (net (code "55") (name "P0.13") (class "Default")
      (node (ref "C30") (pin "2") (pinfunction "2_2") (pintype "passive"))
      (node (ref "R5") (pin "1") (pinfunction "1_1") (pintype "bidirectional"))
      (node (ref "SW_UP") (pin "2") (pinfunction "2_2") (pintype "passive"))
      (node (ref "U1") (pin "P$AD8") (pinfunction "P0.13_P$AD8") (pintype "bidirectional"))
    )
    (net (code "56") (name "P0.14") (class "Default")
      (node (ref "C31") (pin "2") (pinfunction "2_2") (pintype "passive"))
      (node (ref "R8") (pin "1") (pinfunction "1_1") (pintype "bidirectional"))
      (node (ref "SW_ENT") (pin "2") (pinfunction "2_2") (pintype "passive"))
      (node (ref "U1") (pin "P$AC9") (pinfunction "P0.14_P$AC9") (pintype "bidirectional"))
    )
    (net (code "57") (name "P0.19") (class "Default")
      (node (ref "U1") (pin "P$AC15") (pinfunction "P0.19_P$AC15") (pintype "bidirectional"))
    )
    (net (code "58") (name "P0.20") (class "Default")
      (node (ref "U1") (pin "P$AD16") (pinfunction "P0.20_P$AD16") (pintype "bidirectional"))
    )
    (net (code "59") (name "P0.21") (class "Default")
      (node (ref "U1") (pin "P$AC17") (pinfunction "P0.21_P$AC17") (pintype "bidirectional"))
    )
    (net (code "60") (name "P0.22") (class "Default")
      (node (ref "U1") (pin "P$AD18") (pinfunction "P0.22_P$AD18") (pintype "bidirectional"))
    )
    (net (code "61") (name "P0.23") (class "Default")
      (node (ref "U1") (pin "P$AC19") (pinfunction "P0.23_P$AC19") (pintype "bidirectional"))
    )
    (net (code "62") (name "P0.24") (class "Default")
      (node (ref "U1") (pin "P$AD20") (pinfunction "P0.24_P$AD20") (pintype "bidirectional"))
    )
    (net (code "63") (name "P0.25") (class "Default")
      (node (ref "U1") (pin "P$AC21") (pinfunction "P0.25_P$AC21") (pintype "bidirectional"))
    )
    (net (code "64") (name "P0.26") (class "Default")
      (node (ref "U1") (pin "P$G1") (pinfunction "P0.26_P$G1") (pintype "bidirectional"))
    )
    (net (code "65") (name "P0.27") (class "Default")
      (node (ref "U1") (pin "P$H2") (pinfunction "P0.27_P$H2") (pintype "bidirectional"))
    )
    (net (code "66") (name "P0.28") (class "Default")
      (node (ref "U1") (pin "P$B11") (pinfunction "P0.28/AIN4_P$B11") (pintype "bidirectional"))
    )
    (net (code "67") (name "P0.29") (class "Default")
      (node (ref "U1") (pin "P$A10") (pinfunction "P0.29/AIN5_P$A10") (pintype "bidirectional"))
    )
    (net (code "68") (name "P0.30") (class "Default")
      (node (ref "U1") (pin "P$B9") (pinfunction "P0.30/AIN6_P$B9") (pintype "bidirectional"))
    )
    (net (code "69") (name "P0.31") (class "Default")
      (node (ref "U1") (pin "P$A8") (pinfunction "P0.31/AIN7_P$A8") (pintype "bidirectional"))
    )
    (net (code "70") (name "P1.01") (class "Default")
      (node (ref "Q1") (pin "1") (pinfunction "G_1") (pintype "bidirectional"))
      (node (ref "R_PWR_EPD") (pin "1") (pinfunction "1_1") (pintype "bidirectional"))
      (node (ref "U1") (pin "P$Y23") (pinfunction "P1.01_P$Y23") (pintype "bidirectional"))
    )
    (net (code "71") (name "P1.02") (class "Default")
      (node (ref "C29") (pin "2") (pinfunction "2_2") (pintype "passive"))
      (node (ref "R7") (pin "1") (pinfunction "1_1") (pintype "bidirectional"))
      (node (ref "SW_DN") (pin "2") (pinfunction "2_2") (pintype "passive"))
      (node (ref "U1") (pin "P$W24") (pinfunction "P1.02_P$W24") (pintype "bidirectional"))
    )
    (net (code "72") (name "P1.03") (class "Default")
      (node (ref "U1") (pin "P$V23") (pinfunction "P1.03_P$V23") (pintype "bidirectional"))
    )
    (net (code "73") (name "P1.04") (class "Default")
      (node (ref "U1") (pin "P$U24") (pinfunction "P1.04_P$U24") (pintype "bidirectional"))
    )
    (net (code "74") (name "P1.05") (class "Default")
      (node (ref "U1") (pin "P$T23") (pinfunction "P1.05_P$T23") (pintype "bidirectional"))
    )
    (net (code "75") (name "P1.06") (class "Default")
      (node (ref "U1") (pin "P$R24") (pinfunction "P1.06_P$R24") (pintype "bidirectional"))
    )
    (net (code "76") (name "P1.07") (class "Default")
      (node (ref "U1") (pin "P$P23") (pinfunction "P1.07_P$P23") (pintype "bidirectional"))
    )
    (net (code "77") (name "P1.09") (class "Default")
      (node (ref "U1") (pin "P$R1") (pinfunction "P1.09_P$R1") (pintype "bidirectional"))
    )
    (net (code "78") (name "P1.10") (class "Default")
      (node (ref "U1") (pin "P$A20") (pinfunction "P1.10_P$A20") (pintype "bidirectional"))
    )
    (net (code "79") (name "P1.11") (class "Default")
      (node (ref "U1") (pin "P$B19") (pinfunction "P1.11_P$B19") (pintype "bidirectional"))
    )
    (net (code "80") (name "P1.12") (class "Default")
      (node (ref "U1") (pin "P$B17") (pinfunction "P1.12_P$B17") (pintype "bidirectional"))
    )
    (net (code "81") (name "P1.13") (class "Default")
      (node (ref "U1") (pin "P$A16") (pinfunction "P1.13_P$A16") (pintype "bidirectional"))
    )
    (net (code "82") (name "P1.14") (class "Default")
      (node (ref "U1") (pin "P$B15") (pinfunction "P1.14_P$B15") (pintype "bidirectional"))
    )
    (net (code "83") (name "P1.15") (class "Default")
      (node (ref "U1") (pin "P$A14") (pinfunction "P1.15_P$A14") (pintype "bidirectional"))
    )
    (net (code "84") (name "PMIC_INT") (class "Default")
      (node (ref "IC1") (pin "A1") (pinfunction "~{INT}_A1") (pintype "bidirectional"))
      (node (ref "U1") (pin "P$T2") (pinfunction "P0.11_P$T2") (pintype "bidirectional"))
    )
    (net (code "85") (name "PREVGH") (class "Default")
      (node (ref "D5") (pin "1") (pinfunction "K_1") (pintype "bidirectional"))
      (node (ref "EPD_C9") (pin "1") (pinfunction "1_1") (pintype "passive"))
      (node (ref "J1") (pin "21") (pinfunction "21_21") (pintype "bidirectional"))
    )
    (net (code "86") (name "PREVGL") (class "Default")
      (node (ref "D2") (pin "2") (pinfunction "A_2") (pintype "bidirectional"))
      (node (ref "EPD_C11") (pin "1") (pinfunction "1_1") (pintype "passive"))
      (node (ref "J1") (pin "23") (pinfunction "23_23") (pintype "bidirectional"))
    )
    (net (code "87") (name "RESE") (class "Default")
      (node (ref "J1") (pin "3") (pinfunction "3_3") (pintype "bidirectional"))
      (node (ref "Q3") (pin "2") (pinfunction "S_2") (pintype "bidirectional"))
      (node (ref "R1_EP_DR") (pin "2") (pinfunction "2_2") (pintype "bidirectional"))
    )
    (net (code "88") (name "RESET") (class "Default")
      (node (ref "J2") (pin "6") (pinfunction "6_6") (pintype "bidirectional"))
      (node (ref "TP_RESET") (pin "TP") (pinfunction "TP_TP") (pintype "input"))
      (node (ref "U1") (pin "P$AC13") (pinfunction "P0.18/RESET_P$AC13") (pintype "bidirectional"))
    )
    (net (code "89") (name "SCK") (class "Default")
      (node (ref "J1") (pin "13") (pinfunction "13_13") (pintype "bidirectional"))
      (node (ref "U1") (pin "P$A12") (pinfunction "P0.02/AIN0_P$A12") (pintype "bidirectional"))
    )
    (net (code "90") (name "SCL") (class "Default")
      (node (ref "IC1") (pin "B1") (pinfunction "SCL_B1") (pintype "bidirectional"))
      (node (ref "IC2") (pin "C1") (pinfunction "SCL_C1") (pintype "bidirectional"))
      (node (ref "IC3") (pin "12") (pinfunction "SCX_12") (pintype "bidirectional"))
      (node (ref "R17") (pin "2") (pinfunction "2_2") (pintype "bidirectional"))
      (node (ref "R4") (pin "1") (pinfunction "1_1") (pintype "bidirectional"))
      (node (ref "TP_SCL") (pin "TP") (pinfunction "TP_TP") (pintype "input"))
      (node (ref "U1") (pin "P$M2") (pinfunction "P0.07_P$M2") (pintype "bidirectional"))
      (node (ref "U3") (pin "7") (pinfunction "SCL_7") (pintype "input"))
    )
    (net (code "91") (name "SDA") (class "Default")
      (node (ref "IC1") (pin "C1") (pinfunction "SDA_C1") (pintype "bidirectional"))
      (node (ref "IC2") (pin "B2") (pinfunction "SDA_B2") (pintype "bidirectional"))
      (node (ref "IC3") (pin "2") (pinfunction "SDX_2") (pintype "bidirectional"))
      (node (ref "R18") (pin "2") (pinfunction "2_2") (pintype "bidirectional"))
      (node (ref "R2") (pin "1") (pinfunction "1_1") (pintype "bidirectional"))
      (node (ref "TP_SDA") (pin "TP") (pinfunction "TP_TP") (pintype "input"))
      (node (ref "U1") (pin "P$L1") (pinfunction "P0.06_P$L1") (pintype "bidirectional"))
      (node (ref "U3") (pin "8") (pinfunction "SDA_8") (pintype "bidirectional"))
    )
    (net (code "92") (name "SWDCLK") (class "Default")
      (node (ref "J2") (pin "4") (pinfunction "4_4") (pintype "bidirectional"))
      (node (ref "TP_SWDCLK") (pin "TP") (pinfunction "TP_TP") (pintype "input"))
      (node (ref "U1") (pin "P$AA24") (pinfunction "SWDCLK_P$AA24") (pintype "input"))
    )
    (net (code "93") (name "SWDIO") (class "Default")
      (node (ref "J2") (pin "2") (pinfunction "2_2") (pintype "bidirectional"))
      (node (ref "TP_SWDIO") (pin "TP") (pinfunction "TP_TP") (pintype "input"))
      (node (ref "U1") (pin "P$AC24") (pinfunction "SWDIO_P$AC24") (pintype "bidirectional"))
    )
    (net (code "94") (name "SWO") (class "Default")
      (node (ref "TP_SWO") (pin "TP") (pinfunction "TP_TP") (pintype "input"))
      (node (ref "U1") (pin "P$AD22") (pinfunction "P1.00_P$AD22") (pintype "bidirectional"))
    )
    (net (code "95") (name "VBAT") (class "Default")
      (node (ref "C27") (pin "2") (pinfunction "2_2") (pintype "passive"))
      (node (ref "C37") (pin "2") (pinfunction "2_2") (pintype "passive"))
      (node (ref "IC1") (pin "C2") (pinfunction "BAT_C2") (pintype "bidirectional"))
      (node (ref "TP_VBAT") (pin "TP") (pinfunction "TP_TP") (pintype "input"))
      (node (ref "U3") (pin "2") (pinfunction "CELL_2") (pintype "power_in"))
      (node (ref "U3") (pin "3") (pinfunction "VDD_3") (pintype "power_in"))
    )
    (net (code "96") (name "VBUS") (class "Default")
      (node (ref "C21") (pin "1") (pinfunction "1_1") (pintype "passive"))
      (node (ref "C38") (pin "2") (pinfunction "2_2") (pintype "passive"))
      (node (ref "C42") (pin "1") (pinfunction "1_1") (pintype "passive"))
      (node (ref "C43") (pin "1") (pinfunction "1_1") (pintype "passive"))
      (node (ref "D3") (pin "5") (pinfunction "VBUS_5") (pintype "bidirectional"))
      (node (ref "IC1") (pin "A2") (pinfunction "IN_A2") (pintype "bidirectional"))
      (node (ref "J4") (pin "A4_B9") (pinfunction "VBUS_A4_B9") (pintype "power_in"))
      (node (ref "J4") (pin "A9_B4") (pinfunction "VBUS_A9_B4") (pintype "power_in"))
      (node (ref "U1") (pin "P$AD2") (pinfunction "VBUS_P$AD2") (pintype "power_in"))
    )
    (net (code "97") (name "VREG") (class "Default")
      (node (ref "C23") (pin "2") (pinfunction "2_2") (pintype "passive"))
      (node (ref "C24") (pin "2") (pinfunction "2_2") (pintype "passive"))
      (node (ref "C39") (pin "1") (pinfunction "1_1") (pintype "passive"))
      (node (ref "IC1") (pin "B2") (pinfunction "SYS_B2") (pintype "bidirectional"))
      (node (ref "IC9") (pin "A1") (pinfunction "EN_A1") (pintype "bidirectional"))
      (node (ref "IC9") (pin "A2") (pinfunction "VIN_1_A2") (pintype "bidirectional"))
      (node (ref "IC9") (pin "A3") (pinfunction "VIN_2_A3") (pintype "bidirectional"))
      (node (ref "TP_VREG") (pin "TP") (pinfunction "TP_TP") (pintype "input"))
    )
    (net (code "98") (name "unconnected-(ANT1-NC-Pad2)") (class "Default")
      (node (ref "ANT1") (pin "2") (pinfunction "NC_2") (pintype "no_connect"))
    )
    (net (code "99") (name "unconnected-(IC3-ASCL-Pad11)") (class "Default")
      (node (ref "IC3") (pin "11") (pinfunction "ASCL_11") (pintype "bidirectional"))
    )
    (net (code "100") (name "unconnected-(IC3-ASDA-Pad4)") (class "Default")
      (node (ref "IC3") (pin "4") (pinfunction "ASDA_4") (pintype "bidirectional"))
    )
    (net (code "101") (name "unconnected-(J1-Pad1)") (class "Default")
      (node (ref "J1") (pin "1") (pinfunction "1_1") (pintype "bidirectional"))
    )
    (net (code "102") (name "unconnected-(J1-Pad6)") (class "Default")
      (node (ref "J1") (pin "6") (pinfunction "6_6") (pintype "bidirectional"))
    )
    (net (code "103") (name "unconnected-(J1-Pad7)") (class "Default")
      (node (ref "J1") (pin "7") (pinfunction "7_7") (pintype "bidirectional"))
    )
    (net (code "104") (name "unconnected-(J4-SBU1-PadA8)") (class "Default")
      (node (ref "J4") (pin "A8") (pinfunction "SBU1_A8") (pintype "bidirectional"))
    )
    (net (code "105") (name "unconnected-(J4-SBU2-PadB8)") (class "Default")
      (node (ref "J4") (pin "B8") (pinfunction "SBU2_B8") (pintype "bidirectional"))
    )
    (net (code "106") (name "unconnected-(U1-DCCH-PadP$AB2)") (class "Default")
      (node (ref "U1") (pin "P$AB2") (pinfunction "DCCH_P$AB2") (pintype "bidirectional"))
    )
  )
)
